# MP2225.net
KiCad netlist of a schematic drawn in EAGLE
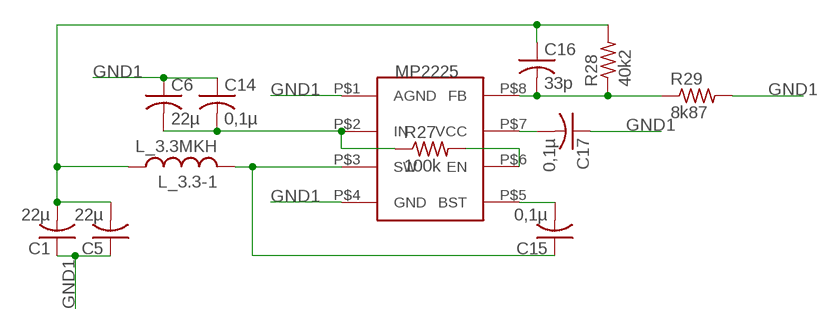
[diagram p0: schematic, sheet 1]

(export (version "E")
  (design (tool "Eeschema 10.0.6"))
  (components
    (comp (ref "C1")
      (value "22µ")
      (footprint "eagle-import:C1206")
      (libsource (lib "eagle-import") (part "C-USC1206"))
    )
    (comp (ref "C5")
      (value "22µ")
      (footprint "eagle-import:C1206")
      (libsource (lib "eagle-import") (part "C-USC1206"))
    )
    (comp (ref "C6")
      (value "22µ")
      (footprint "eagle-import:C1206")
      (libsource (lib "eagle-import") (part "C-USC1206"))
    )
    (comp (ref "C14")
      (value "0,1µ")
      (footprint "eagle-import:C0603")
      (libsource (lib "eagle-import") (part "C-USC0603"))
    )
    (comp (ref "C15")
      (value "0,1µ")
      (footprint "eagle-import:C0603")
      (libsource (lib "eagle-import") (part "C-USC0603"))
    )
    (comp (ref "C16")
      (value "33p")
      (footprint "eagle-import:C0603")
      (libsource (lib "eagle-import") (part "C-USC0603"))
    )
    (comp (ref "C17")
      (value "0,1µ")
      (footprint "eagle-import:C0603")
      (libsource (lib "eagle-import") (part "C-USC0603"))
    )
    (comp (ref "L_3.3-1")
      (value "L_3.3MKH")
      (footprint "eagle-import:L_SPM5020")
      (libsource (lib "eagle-import") (part "L_3.3MKH_5X5"))
    )
    (comp (ref "MP2225-1")
      (value "MP2225")
      (footprint "eagle-import:TSOT23-8")
      (libsource (lib "eagle-import") (part "MP2225"))
    )
    (comp (ref "R27")
      (value "100k")
      (footprint "eagle-import:R0603")
      (libsource (lib "eagle-import") (part "R-US_R0603"))
    )
    (comp (ref "R28")
      (value "40k2")
      (footprint "eagle-import:R0603")
      (libsource (lib "eagle-import") (part "R-US_R0603"))
    )
    (comp (ref "R29")
      (value "8k87")
      (footprint "eagle-import:R0603")
      (libsource (lib "eagle-import") (part "R-US_R0603"))
    )
  )
  (nets
    (net (code "1") (name "/GND1") (class "Default")
      (node (ref "C1") (pin "1") (pinfunction "1_1") (pintype "passive"))
      (node (ref "C14") (pin "1") (pinfunction "1_1") (pintype "passive"))
      (node (ref "C17") (pin "1") (pinfunction "1_1") (pintype "passive"))
      (node (ref "C5") (pin "1") (pinfunction "1_1") (pintype "passive"))
      (node (ref "C6") (pin "1") (pinfunction "1_1") (pintype "passive"))
      (node (ref "MP2225-1") (pin "P$1") (pinfunction "AGND_P$1") (pintype "bidirectional"))
      (node (ref "MP2225-1") (pin "P$4") (pinfunction "GND_P$4") (pintype "bidirectional"))
      (node (ref "R29") (pin "2") (pinfunction "2_2") (pintype "passive"))
    )
    (net (code "2") (name "Net-(L_3.3-1-1)") (class "Default")
      (node (ref "C1") (pin "2") (pinfunction "2_2") (pintype "passive"))
      (node (ref "C16") (pin "1") (pinfunction "1_1") (pintype "passive"))
      (node (ref "C5") (pin "2") (pinfunction "2_2") (pintype "passive"))
      (node (ref "L_3.3-1") (pin "P$1") (pinfunction "1_P$1") (pintype "passive"))
      (node (ref "R28") (pin "2") (pinfunction "2_2") (pintype "passive"))
    )
    (net (code "3") (name "Net-(L_3.3-1-2)") (class "Default")
      (node (ref "C15") (pin "1") (pinfunction "1_1") (pintype "passive"))
      (node (ref "L_3.3-1") (pin "P$2") (pinfunction "2_P$2") (pintype "passive"))
      (node (ref "MP2225-1") (pin "P$3") (pinfunction "SW_P$3") (pintype "bidirectional"))
    )
    (net (code "4") (name "Net-(MP2225-1-BST)") (class "Default")
      (node (ref "C15") (pin "2") (pinfunction "2_2") (pintype "passive"))
      (node (ref "MP2225-1") (pin "P$5") (pinfunction "BST_P$5") (pintype "bidirectional"))
    )
    (net (code "5") (name "Net-(MP2225-1-EN)") (class "Default")
      (node (ref "MP2225-1") (pin "P$6") (pinfunction "EN_P$6") (pintype "bidirectional"))
      (node (ref "R27") (pin "2") (pinfunction "2_2") (pintype "passive"))
    )
    (net (code "6") (name "Net-(MP2225-1-FB)") (class "Default")
      (node (ref "C16") (pin "2") (pinfunction "2_2") (pintype "passive"))
      (node (ref "MP2225-1") (pin "P$8") (pinfunction "FB_P$8") (pintype "bidirectional"))
      (node (ref "R28") (pin "1") (pinfunction "1_1") (pintype "passive"))
      (node (ref "R29") (pin "1") (pinfunction "1_1") (pintype "passive"))
    )
    (net (code "7") (name "Net-(MP2225-1-IN)") (class "Default")
      (node (ref "C14") (pin "2") (pinfunction "2_2") (pintype "passive"))
      (node (ref "C6") (pin "2") (pinfunction "2_2") (pintype "passive"))
      (node (ref "MP2225-1") (pin "P$2") (pinfunction "IN_P$2") (pintype "bidirectional"))
      (node (ref "R27") (pin "1") (pinfunction "1_1") (pintype "passive"))
    )
    (net (code "8") (name "Net-(MP2225-1-VCC)") (class "Default")
      (node (ref "C17") (pin "2") (pinfunction "2_2") (pintype "passive"))
      (node (ref "MP2225-1") (pin "P$7") (pinfunction "VCC_P$7") (pintype "bidirectional"))
    )
  )
)
